# ARDUINO.net
KiCad netlist of a schematic drawn in EAGLE
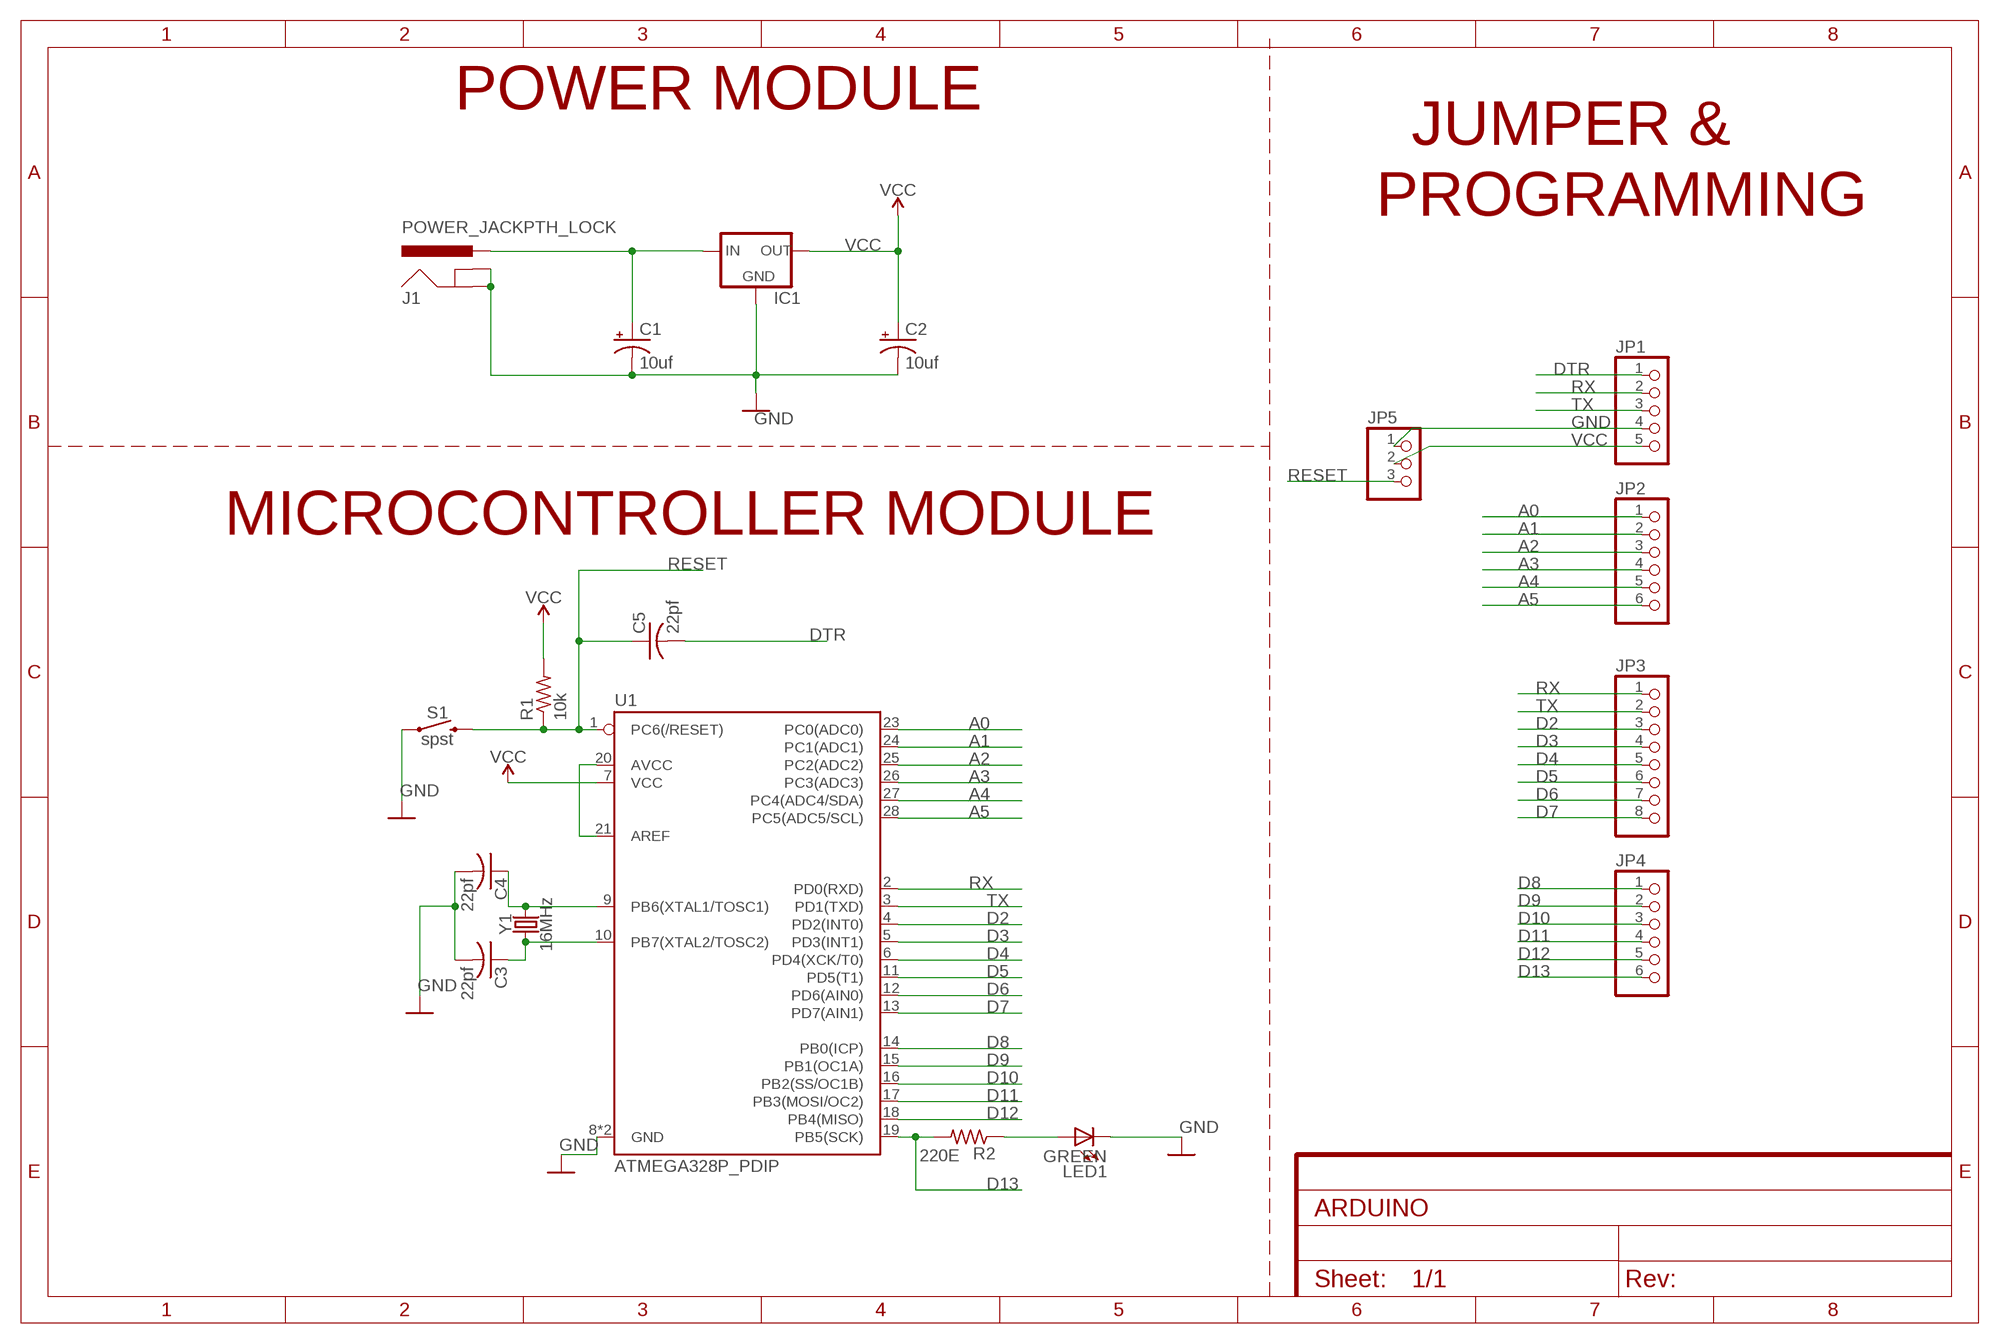
[diagram p0: schematic, sheet 1]

(export (version "E")
  (design (tool "Eeschema 10.0.6"))
  (components
    (comp (ref "C1")
      (value "10uf")
      (footprint "eagle-import:E2,5-6E")
      (libsource (lib "eagle-import") (part "CPOL-USE2,5-6E"))
    )
    (comp (ref "C2")
      (value "10uf")
      (footprint "eagle-import:E2,5-6E")
      (libsource (lib "eagle-import") (part "CPOL-USE2,5-6E"))
    )
    (comp (ref "C3")
      (value "22pf")
      (footprint "eagle-import:C025-024X044")
      (libsource (lib "eagle-import") (part "C-US025-024X044"))
    )
    (comp (ref "C4")
      (value "22pf")
      (footprint "eagle-import:C025-024X044")
      (libsource (lib "eagle-import") (part "C-US025-024X044"))
    )
    (comp (ref "C5")
      (value "22pf")
      (footprint "eagle-import:C025-024X044")
      (libsource (lib "eagle-import") (part "C-US025-024X044"))
    )
    (comp (ref "IC1")
      (value "MCP1700TRI")
      (footprint "eagle-import:TO92")
      (libsource (lib "eagle-import") (part "MCP1700TRI"))
    )
    (comp (ref "J1")
      (value "POWER_JACKPTH_LOCK")
      (footprint "eagle-import:POWER_JACK_PTH_LOCK")
      (libsource (lib "eagle-import") (part "POWER_JACKPTH_LOCK"))
    )
    (comp (ref "JP1")
      (value "PINHD-1X5")
      (footprint "eagle-import:1X05")
      (libsource (lib "eagle-import") (part "PINHD-1X5"))
    )
    (comp (ref "JP2")
      (value "PINHD-1X6")
      (footprint "eagle-import:1X06")
      (libsource (lib "eagle-import") (part "PINHD-1X6"))
    )
    (comp (ref "JP3")
      (value "PINHD-1X8")
      (footprint "eagle-import:1X08")
      (libsource (lib "eagle-import") (part "PINHD-1X8"))
    )
    (comp (ref "JP4")
      (value "PINHD-1X6")
      (footprint "eagle-import:1X06")
      (libsource (lib "eagle-import") (part "PINHD-1X6"))
    )
    (comp (ref "JP5")
      (value "PINHD-1X3")
      (footprint "eagle-import:1X03")
      (libsource (lib "eagle-import") (part "PINHD-1X3"))
    )
    (comp (ref "LED1")
      (value "GREEN")
      (footprint "eagle-import:LED3MM")
      (libsource (lib "eagle-import") (part "LED3MM"))
    )
    (comp (ref "R1")
      (value "10k")
      (footprint "eagle-import:0204_7")
      (libsource (lib "eagle-import") (part "R-US_0204/7"))
    )
    (comp (ref "R2")
      (value "220E")
      (footprint "eagle-import:0204_7")
      (libsource (lib "eagle-import") (part "R-US_0204/7"))
    )
    (comp (ref "S1")
      (value "spst")
      (footprint "eagle-import:TACTILE_SWITCH_PTH_6.0MM")
      (libsource (lib "eagle-import") (part "MOMENTARY-SWITCH-SPST-PTH-6.0MM"))
    )
    (comp (ref "U1")
      (value "ATMEGA328P_PDIP")
      (footprint "eagle-import:DIP28")
      (libsource (lib "eagle-import") (part "ATMEGA328P_PDIP"))
    )
    (comp (ref "Y1")
      (value "16MHz")
      (footprint "eagle-import:HC49US")
      (libsource (lib "eagle-import") (part "CRYSTAL-16MHZPTH-HC49US"))
    )
  )
  (nets
    (net (code "1") (name "/A0") (class "Default")
      (node (ref "JP2") (pin "1") (pinfunction "1_1") (pintype "passive"))
      (node (ref "U1") (pin "23") (pinfunction "PC0(ADC0)_23") (pintype "bidirectional"))
    )
    (net (code "2") (name "/A1") (class "Default")
      (node (ref "JP2") (pin "2") (pinfunction "2_2") (pintype "passive"))
      (node (ref "U1") (pin "24") (pinfunction "PC1(ADC1)_24") (pintype "bidirectional"))
    )
    (net (code "3") (name "/A2") (class "Default")
      (node (ref "JP2") (pin "3") (pinfunction "3_3") (pintype "passive"))
      (node (ref "U1") (pin "25") (pinfunction "PC2(ADC2)_25") (pintype "bidirectional"))
    )
    (net (code "4") (name "/A3") (class "Default")
      (node (ref "JP2") (pin "4") (pinfunction "4_4") (pintype "passive"))
      (node (ref "U1") (pin "26") (pinfunction "PC3(ADC3)_26") (pintype "bidirectional"))
    )
    (net (code "5") (name "/A4") (class "Default")
      (node (ref "JP2") (pin "5") (pinfunction "5_5") (pintype "passive"))
      (node (ref "U1") (pin "27") (pinfunction "PC4(ADC4/SDA)_27") (pintype "bidirectional"))
    )
    (net (code "6") (name "/A5") (class "Default")
      (node (ref "JP2") (pin "6") (pinfunction "6_6") (pintype "passive"))
      (node (ref "U1") (pin "28") (pinfunction "PC5(ADC5/SCL)_28") (pintype "bidirectional"))
    )
    (net (code "7") (name "/D2") (class "Default")
      (node (ref "JP3") (pin "3") (pinfunction "3_3") (pintype "passive"))
      (node (ref "U1") (pin "4") (pinfunction "PD2(INT0)_4") (pintype "bidirectional"))
    )
    (net (code "8") (name "/D3") (class "Default")
      (node (ref "JP3") (pin "4") (pinfunction "4_4") (pintype "passive"))
      (node (ref "U1") (pin "5") (pinfunction "PD3(INT1)_5") (pintype "bidirectional"))
    )
    (net (code "9") (name "/D4") (class "Default")
      (node (ref "JP3") (pin "5") (pinfunction "5_5") (pintype "passive"))
      (node (ref "U1") (pin "6") (pinfunction "PD4(XCK/T0)_6") (pintype "bidirectional"))
    )
    (net (code "10") (name "/D5") (class "Default")
      (node (ref "JP3") (pin "6") (pinfunction "6_6") (pintype "passive"))
      (node (ref "U1") (pin "11") (pinfunction "PD5(T1)_11") (pintype "bidirectional"))
    )
    (net (code "11") (name "/D6") (class "Default")
      (node (ref "JP3") (pin "7") (pinfunction "7_7") (pintype "passive"))
      (node (ref "U1") (pin "12") (pinfunction "PD6(AIN0)_12") (pintype "bidirectional"))
    )
    (net (code "12") (name "/D7") (class "Default")
      (node (ref "JP3") (pin "8") (pinfunction "8_8") (pintype "passive"))
      (node (ref "U1") (pin "13") (pinfunction "PD7(AIN1)_13") (pintype "bidirectional"))
    )
    (net (code "13") (name "/D8") (class "Default")
      (node (ref "JP4") (pin "1") (pinfunction "1_1") (pintype "passive"))
      (node (ref "U1") (pin "14") (pinfunction "PB0(ICP)_14") (pintype "bidirectional"))
    )
    (net (code "14") (name "/D9") (class "Default")
      (node (ref "JP4") (pin "2") (pinfunction "2_2") (pintype "passive"))
      (node (ref "U1") (pin "15") (pinfunction "PB1(OC1A)_15") (pintype "bidirectional"))
    )
    (net (code "15") (name "/D10") (class "Default")
      (node (ref "JP4") (pin "3") (pinfunction "3_3") (pintype "passive"))
      (node (ref "U1") (pin "16") (pinfunction "PB2(SS/OC1B)_16") (pintype "bidirectional"))
    )
    (net (code "16") (name "/D11") (class "Default")
      (node (ref "JP4") (pin "4") (pinfunction "4_4") (pintype "passive"))
      (node (ref "U1") (pin "17") (pinfunction "PB3(MOSI/OC2)_17") (pintype "bidirectional"))
    )
    (net (code "17") (name "/D12") (class "Default")
      (node (ref "JP4") (pin "5") (pinfunction "5_5") (pintype "passive"))
      (node (ref "U1") (pin "18") (pinfunction "PB4(MISO)_18") (pintype "bidirectional"))
    )
    (net (code "18") (name "/D13") (class "Default")
      (node (ref "JP4") (pin "6") (pinfunction "6_6") (pintype "passive"))
      (node (ref "R2") (pin "2") (pinfunction "2_2") (pintype "passive"))
      (node (ref "U1") (pin "19") (pinfunction "PB5(SCK)_19") (pintype "bidirectional"))
    )
    (net (code "19") (name "/DTR") (class "Default")
      (node (ref "C5") (pin "2") (pinfunction "2_2") (pintype "passive"))
      (node (ref "JP1") (pin "1") (pinfunction "1_1") (pintype "passive"))
    )
    (net (code "20") (name "/RESET") (class "Default")
      (node (ref "C5") (pin "1") (pinfunction "1_1") (pintype "passive"))
      (node (ref "JP5") (pin "3") (pinfunction "3_3") (pintype "passive"))
      (node (ref "R1") (pin "1") (pinfunction "1_1") (pintype "passive"))
      (node (ref "S1") (pin "3") (pinfunction "2_3") (pintype "passive"))
      (node (ref "U1") (pin "1") (pinfunction "PC6(/RESET)_1") (pintype "bidirectional"))
    )
    (net (code "21") (name "/RX") (class "Default")
      (node (ref "JP1") (pin "2") (pinfunction "2_2") (pintype "passive"))
      (node (ref "JP3") (pin "1") (pinfunction "1_1") (pintype "passive"))
      (node (ref "U1") (pin "2") (pinfunction "PD0(RXD)_2") (pintype "bidirectional"))
    )
    (net (code "22") (name "/TX") (class "Default")
      (node (ref "JP1") (pin "3") (pinfunction "3_3") (pintype "passive"))
      (node (ref "JP3") (pin "2") (pinfunction "2_2") (pintype "passive"))
      (node (ref "U1") (pin "3") (pinfunction "PD1(TXD)_3") (pintype "bidirectional"))
    )
    (net (code "23") (name "GND") (class "Default")
      (node (ref "C1") (pin "-") (pinfunction "-_-") (pintype "passive"))
      (node (ref "C2") (pin "-") (pinfunction "-_-") (pintype "passive"))
      (node (ref "C3") (pin "2") (pinfunction "2_2") (pintype "passive"))
      (node (ref "C4") (pin "2") (pinfunction "2_2") (pintype "passive"))
      (node (ref "IC1") (pin "1") (pinfunction "GND_1") (pintype "input"))
      (node (ref "J1") (pin "GND") (pinfunction "GND_GND") (pintype "bidirectional"))
      (node (ref "J1") (pin "GNDBREAK") (pinfunction "GNDBREAK_GNDBREAK") (pintype "bidirectional"))
      (node (ref "JP1") (pin "4") (pinfunction "4_4") (pintype "passive"))
      (node (ref "JP5") (pin "1") (pinfunction "1_1") (pintype "passive"))
      (node (ref "LED1") (pin "K") (pinfunction "C_K") (pintype "passive"))
      (node (ref "S1") (pin "1") (pinfunction "1_1") (pintype "passive"))
      (node (ref "U1") (pin "22") (pinfunction "GND_22") (pintype "bidirectional"))
      (node (ref "U1") (pin "8") (pinfunction "GND_8") (pintype "bidirectional"))
    )
    (net (code "24") (name "Net-(IC1-IN)") (class "Default")
      (node (ref "C1") (pin "+") (pinfunction "+_+") (pintype "passive"))
      (node (ref "IC1") (pin "2") (pinfunction "IN_2") (pintype "input"))
      (node (ref "J1") (pin "PWR") (pinfunction "PWR_PWR") (pintype "bidirectional"))
    )
    (net (code "25") (name "Net-(LED1-PadA)") (class "Default")
      (node (ref "LED1") (pin "A") (pinfunction "A_A") (pintype "passive"))
      (node (ref "R2") (pin "1") (pinfunction "1_1") (pintype "passive"))
    )
    (net (code "26") (name "Net-(U1-AREF)") (class "Default")
      (node (ref "U1") (pin "20") (pinfunction "AVCC_20") (pintype "bidirectional"))
      (node (ref "U1") (pin "21") (pinfunction "AREF_21") (pintype "bidirectional"))
    )
    (net (code "27") (name "Net-(U1-PB6(XTAL1{slash}TOSC1))") (class "Default")
      (node (ref "C4") (pin "1") (pinfunction "1_1") (pintype "passive"))
      (node (ref "U1") (pin "9") (pinfunction "PB6(XTAL1/TOSC1)_9") (pintype "bidirectional"))
      (node (ref "Y1") (pin "2") (pinfunction "2_2") (pintype "passive"))
    )
    (net (code "28") (name "Net-(U1-PB7(XTAL2{slash}TOSC2))") (class "Default")
      (node (ref "C3") (pin "1") (pinfunction "1_1") (pintype "passive"))
      (node (ref "U1") (pin "10") (pinfunction "PB7(XTAL2/TOSC2)_10") (pintype "bidirectional"))
      (node (ref "Y1") (pin "1") (pinfunction "1_1") (pintype "passive"))
    )
    (net (code "29") (name "VCC") (class "Default")
      (node (ref "C2") (pin "+") (pinfunction "+_+") (pintype "passive"))
      (node (ref "IC1") (pin "3") (pinfunction "OUT_3") (pintype "passive"))
      (node (ref "JP1") (pin "5") (pinfunction "5_5") (pintype "passive"))
      (node (ref "JP5") (pin "2") (pinfunction "2_2") (pintype "passive"))
      (node (ref "R1") (pin "2") (pinfunction "2_2") (pintype "passive"))
      (node (ref "U1") (pin "7") (pinfunction "VCC_7") (pintype "bidirectional"))
    )
  )
)
